# nRF24L01.net
KiCad netlist of a schematic drawn in Altium Designer
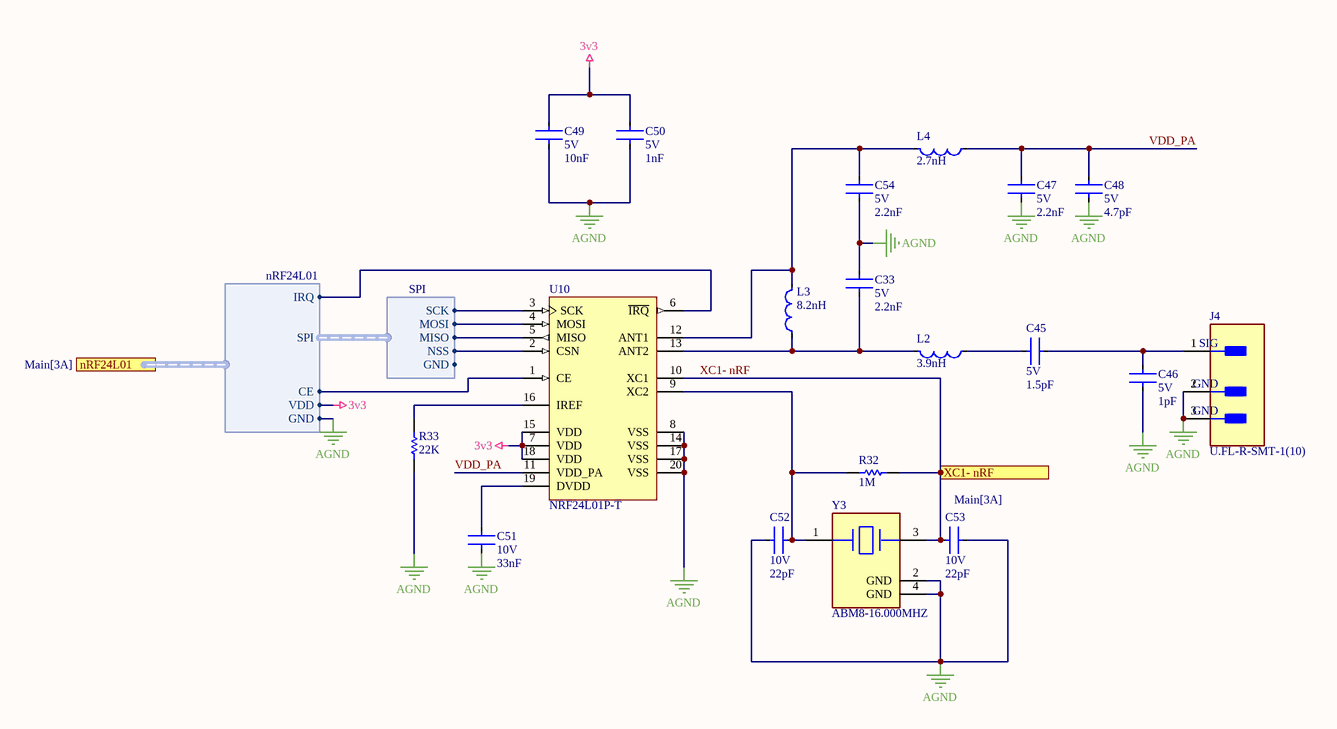
[diagram p0: nRF24L01.SchDoc]

(export (version "E")
  (design (tool "Eeschema 10.0.6"))
  (components
    (comp (ref "C33")
      (value "2.2nF")
      (footprint "CAP-0603-IPC_B")
      (description "Multilayer Ceramic Capacitors")
      (fields (field (name "VOLTAGE") "5V") (field (name "CAPACITANCE") "2.2nF"))
      (libsource (lib "Hosein_PCB_Lib") (part "CAP-Ceramic"))
    )
    (comp (ref "C45")
      (value "1.5pF")
      (footprint "CAP-0603-IPC_B")
      (description "Multilayer Ceramic Capacitors")
      (fields (field (name "VOLTAGE") "5V") (field (name "CAPACITANCE") "1.5pF"))
      (libsource (lib "Hosein_PCB_Lib") (part "CAP-Ceramic"))
    )
    (comp (ref "C46")
      (value "1pF")
      (footprint "CAP-0603-IPC_B")
      (description "Multilayer Ceramic Capacitors")
      (fields (field (name "VOLTAGE") "5V") (field (name "CAPACITANCE") "1pF"))
      (libsource (lib "Hosein_PCB_Lib") (part "CAP-Ceramic"))
    )
    (comp (ref "C47")
      (value "2.2nF")
      (footprint "CAP-0603-IPC_B")
      (description "Multilayer Ceramic Capacitors")
      (fields (field (name "VOLTAGE") "5V") (field (name "CAPACITANCE") "2.2nF"))
      (libsource (lib "Hosein_PCB_Lib") (part "CAP-Ceramic"))
    )
    (comp (ref "C48")
      (value "4.7pF")
      (footprint "CAP-0603-IPC_B")
      (description "Multilayer Ceramic Capacitors")
      (fields (field (name "VOLTAGE") "5V") (field (name "CAPACITANCE") "4.7pF"))
      (libsource (lib "Hosein_PCB_Lib") (part "CAP-Ceramic"))
    )
    (comp (ref "C49")
      (value "10nF")
      (footprint "CAP-0603-IPC_B")
      (description "Multilayer Ceramic Capacitors")
      (fields (field (name "VOLTAGE") "5V") (field (name "CAPACITANCE") "10nF"))
      (libsource (lib "Hosein_PCB_Lib") (part "CAP-Ceramic"))
    )
    (comp (ref "C50")
      (value "1nF")
      (footprint "CAP-0603-IPC_B")
      (description "Multilayer Ceramic Capacitors")
      (fields (field (name "VOLTAGE") "5V") (field (name "CAPACITANCE") "1nF"))
      (libsource (lib "Hosein_PCB_Lib") (part "CAP-Ceramic"))
    )
    (comp (ref "C51")
      (value "33nF")
      (footprint "CAP-0603-IPC_B")
      (description "Multilayer Ceramic Capacitors")
      (fields (field (name "VOLTAGE") "10V") (field (name "CAPACITANCE") "33nF"))
      (libsource (lib "Hosein_PCB_Lib") (part "CAP-Ceramic"))
    )
    (comp (ref "C52")
      (value "22pF")
      (footprint "CAP-0402-IPC_B")
      (description "Multilayer Ceramic Capacitors")
      (fields (field (name "VOLTAGE") "10V") (field (name "CAPACITANCE") "22pF"))
      (libsource (lib "Hosein_PCB_Lib") (part "CAP-Ceramic"))
    )
    (comp (ref "C53")
      (value "22pF")
      (footprint "CAP-0402-IPC_B")
      (description "Multilayer Ceramic Capacitors")
      (fields (field (name "VOLTAGE") "10V") (field (name "CAPACITANCE") "22pF"))
      (libsource (lib "Hosein_PCB_Lib") (part "CAP-Ceramic"))
    )
    (comp (ref "C54")
      (value "2.2nF")
      (footprint "CAP-0603-IPC_B")
      (description "Multilayer Ceramic Capacitors")
      (fields (field (name "VOLTAGE") "5V") (field (name "CAPACITANCE") "2.2nF"))
      (libsource (lib "Hosein_PCB_Lib") (part "CAP-Ceramic"))
    )
    (comp (ref "J4")
      (value "U.FL-R-SMT-1(10)")
      (footprint "Connectors Header:Hirose U.FL_SMT-1_10-MFG")
      (description "CONN U.FL RCPT STR 50 OHM SMD\r\nRF connector for high-frequency signals up to 6 GHz")
      (libsource (lib "Connectors Header") (part "Hirose U.FL"))
    )
    (comp (ref "L2")
      (value "3.9nH")
      (footprint "ind-0603-IPC_B")
      (description "Inductor")
      (libsource (lib "Hosein_PCB_Lib") (part "inductor"))
    )
    (comp (ref "L3")
      (value "8.2nH")
      (footprint "ind-0603-IPC_B")
      (description "Inductor")
      (libsource (lib "Hosein_PCB_Lib") (part "inductor"))
    )
    (comp (ref "L4")
      (value "2.7nH")
      (footprint "ind-0603-IPC_B")
      (description "Inductor")
      (libsource (lib "Hosein_PCB_Lib") (part "inductor"))
    )
    (comp (ref "R32")
      (value "1M")
      (footprint "RES-0402-IPC_B")
      (description "Chip Resistor")
      (libsource (lib "Hosein_PCB_Lib") (part "RES_SMD"))
    )
    (comp (ref "R33")
      (value "22K")
      (footprint "RES-0603-IPC_B")
      (description "Chip Resistor")
      (libsource (lib "Hosein_PCB_Lib") (part "RES_SMD"))
    )
    (comp (ref "U10")
      (value "NRF24L01P-T")
      (footprint "NRSC-QFN-20_L")
      (description "Single Chip Transceiver, 2.4 GHz, 60 mW, 1.9 to 3.6 V, -40 to 85 degC, 20-Pin QFN, RoHS, Tray")
      (fields (field (name "MANUFACTURER") "Nordic Semiconductor"))
      (libsource (lib "Altium Content Vault") (part "NRSC-NRF24L01P-QFN-20"))
    )
    (comp (ref "Y3")
      (value "ABM8-16.000MHZ")
      (footprint "ABM8-Xtal-MFG")
      (description "Crystal 16MHz ±10ppm 7pF SMD-4 3.2mm x 2.5mm")
      (libsource (lib "Hosein_PCB_Lib") (part "Crystal"))
    )
  )
  (nets
    (net (code "3") (name "/CE") (class "Default")
      (node (ref "U10") (pin "1") (pinfunction "CE_1") (pintype "input"))
    )
    (net (code "4") (name "/IRQ") (class "Default")
      (node (ref "U10") (pin "6") (pinfunction "~{IRQ}_6") (pintype "output"))
    )
    (net (code "5") (name "/MISO") (class "Default")
      (node (ref "U10") (pin "5") (pinfunction "MISO_5") (pintype "output"))
    )
    (net (code "6") (name "/MOSI") (class "Default")
      (node (ref "U10") (pin "4") (pinfunction "MOSI_4") (pintype "input"))
    )
    (net (code "7") (name "/NSS") (class "Default")
      (node (ref "U10") (pin "2") (pinfunction "CSN_2") (pintype "input"))
    )
    (net (code "8") (name "/SCK") (class "Default")
      (node (ref "U10") (pin "3") (pinfunction "SCK_3") (pintype "input"))
    )
    (net (code "9") (name "/VDD_PA") (class "Default")
      (node (ref "C47") (pin "2") (pinfunction "2_2") (pintype "passive"))
      (node (ref "C48") (pin "1") (pinfunction "1_1") (pintype "passive"))
      (node (ref "L4") (pin "2") (pinfunction "2_2") (pintype "passive"))
      (node (ref "U10") (pin "11") (pinfunction "VDD_PA_11") (pintype "power_in"))
    )
    (net (code "10") (name "/XC1- nRF") (class "Default")
      (node (ref "C53") (pin "1") (pinfunction "1_1") (pintype "passive"))
      (node (ref "R32") (pin "2") (pinfunction "2_2") (pintype "passive"))
      (node (ref "U10") (pin "10") (pinfunction "XC1_10") (pintype "passive"))
      (node (ref "Y3") (pin "3") (pinfunction "3_3") (pintype "passive"))
    )
    (net (code "13") (name "3v3") (class "Default")
      (node (ref "C49") (pin "1") (pinfunction "1_1") (pintype "passive"))
      (node (ref "C50") (pin "1") (pinfunction "1_1") (pintype "passive"))
      (node (ref "U10") (pin "15") (pinfunction "VDD_15") (pintype "power_in"))
      (node (ref "U10") (pin "18") (pinfunction "VDD_18") (pintype "power_in"))
      (node (ref "U10") (pin "7") (pinfunction "VDD_7") (pintype "power_in"))
    )
    (net (code "14") (name "AGND") (class "Default")
      (node (ref "C33") (pin "2") (pinfunction "2_2") (pintype "passive"))
      (node (ref "C46") (pin "1") (pinfunction "1_1") (pintype "passive"))
      (node (ref "C47") (pin "1") (pinfunction "1_1") (pintype "passive"))
      (node (ref "C48") (pin "2") (pinfunction "2_2") (pintype "passive"))
      (node (ref "C49") (pin "2") (pinfunction "2_2") (pintype "passive"))
      (node (ref "C50") (pin "2") (pinfunction "2_2") (pintype "passive"))
      (node (ref "C51") (pin "2") (pinfunction "2_2") (pintype "passive"))
      (node (ref "C52") (pin "1") (pinfunction "1_1") (pintype "passive"))
      (node (ref "C53") (pin "2") (pinfunction "2_2") (pintype "passive"))
      (node (ref "C54") (pin "1") (pinfunction "1_1") (pintype "passive"))
      (node (ref "J4") (pin "2") (pinfunction "GND_2") (pintype "power_in"))
      (node (ref "J4") (pin "3") (pinfunction "GND_3") (pintype "power_in"))
      (node (ref "R33") (pin "2") (pinfunction "2_2") (pintype "passive"))
      (node (ref "U10") (pin "14") (pinfunction "VSS_14") (pintype "power_in"))
      (node (ref "U10") (pin "17") (pinfunction "VSS_17") (pintype "power_in"))
      (node (ref "U10") (pin "20") (pinfunction "VSS_20") (pintype "power_in"))
      (node (ref "U10") (pin "8") (pinfunction "VSS_8") (pintype "power_in"))
      (node (ref "Y3") (pin "2") (pinfunction "GND_2") (pintype "power_in"))
      (node (ref "Y3") (pin "4") (pinfunction "GND_4") (pintype "power_in"))
    )
    (net (code "15") (name "Net-(C45-Pad1)") (class "Default")
      (node (ref "C45") (pin "1") (pinfunction "1_1") (pintype "passive"))
      (node (ref "L2") (pin "2") (pinfunction "2_2") (pintype "passive"))
    )
    (net (code "16") (name "Net-(J4-SIG)") (class "Default")
      (node (ref "C45") (pin "2") (pinfunction "2_2") (pintype "passive"))
      (node (ref "C46") (pin "2") (pinfunction "2_2") (pintype "passive"))
      (node (ref "J4") (pin "1") (pinfunction "SIG_1") (pintype "passive"))
    )
    (net (code "17") (name "Net-(U10-ANT1)") (class "Default")
      (node (ref "C54") (pin "2") (pinfunction "2_2") (pintype "passive"))
      (node (ref "L3") (pin "1") (pinfunction "1_1") (pintype "passive"))
      (node (ref "L4") (pin "1") (pinfunction "1_1") (pintype "passive"))
      (node (ref "U10") (pin "12") (pinfunction "ANT1_12") (pintype "passive"))
    )
    (net (code "18") (name "Net-(U10-ANT2)") (class "Default")
      (node (ref "C33") (pin "1") (pinfunction "1_1") (pintype "passive"))
      (node (ref "L2") (pin "1") (pinfunction "1_1") (pintype "passive"))
      (node (ref "L3") (pin "2") (pinfunction "2_2") (pintype "passive"))
      (node (ref "U10") (pin "13") (pinfunction "ANT2_13") (pintype "passive"))
    )
    (net (code "19") (name "Net-(U10-DVDD)") (class "Default")
      (node (ref "C51") (pin "1") (pinfunction "1_1") (pintype "passive"))
      (node (ref "U10") (pin "19") (pinfunction "DVDD_19") (pintype "power_in"))
    )
    (net (code "20") (name "Net-(U10-IREF)") (class "Default")
      (node (ref "R33") (pin "1") (pinfunction "1_1") (pintype "passive"))
      (node (ref "U10") (pin "16") (pinfunction "IREF_16") (pintype "passive"))
    )
    (net (code "21") (name "Net-(U10-XC2)") (class "Default")
      (node (ref "C52") (pin "2") (pinfunction "2_2") (pintype "passive"))
      (node (ref "R32") (pin "1") (pinfunction "1_1") (pintype "passive"))
      (node (ref "U10") (pin "9") (pinfunction "XC2_9") (pintype "passive"))
      (node (ref "Y3") (pin "1") (pinfunction "1_1") (pintype "passive"))
    )
  )
)
